# ProPrj___2025-03-14.net
KiCad netlist of a schematic drawn in EasyEDA Pro
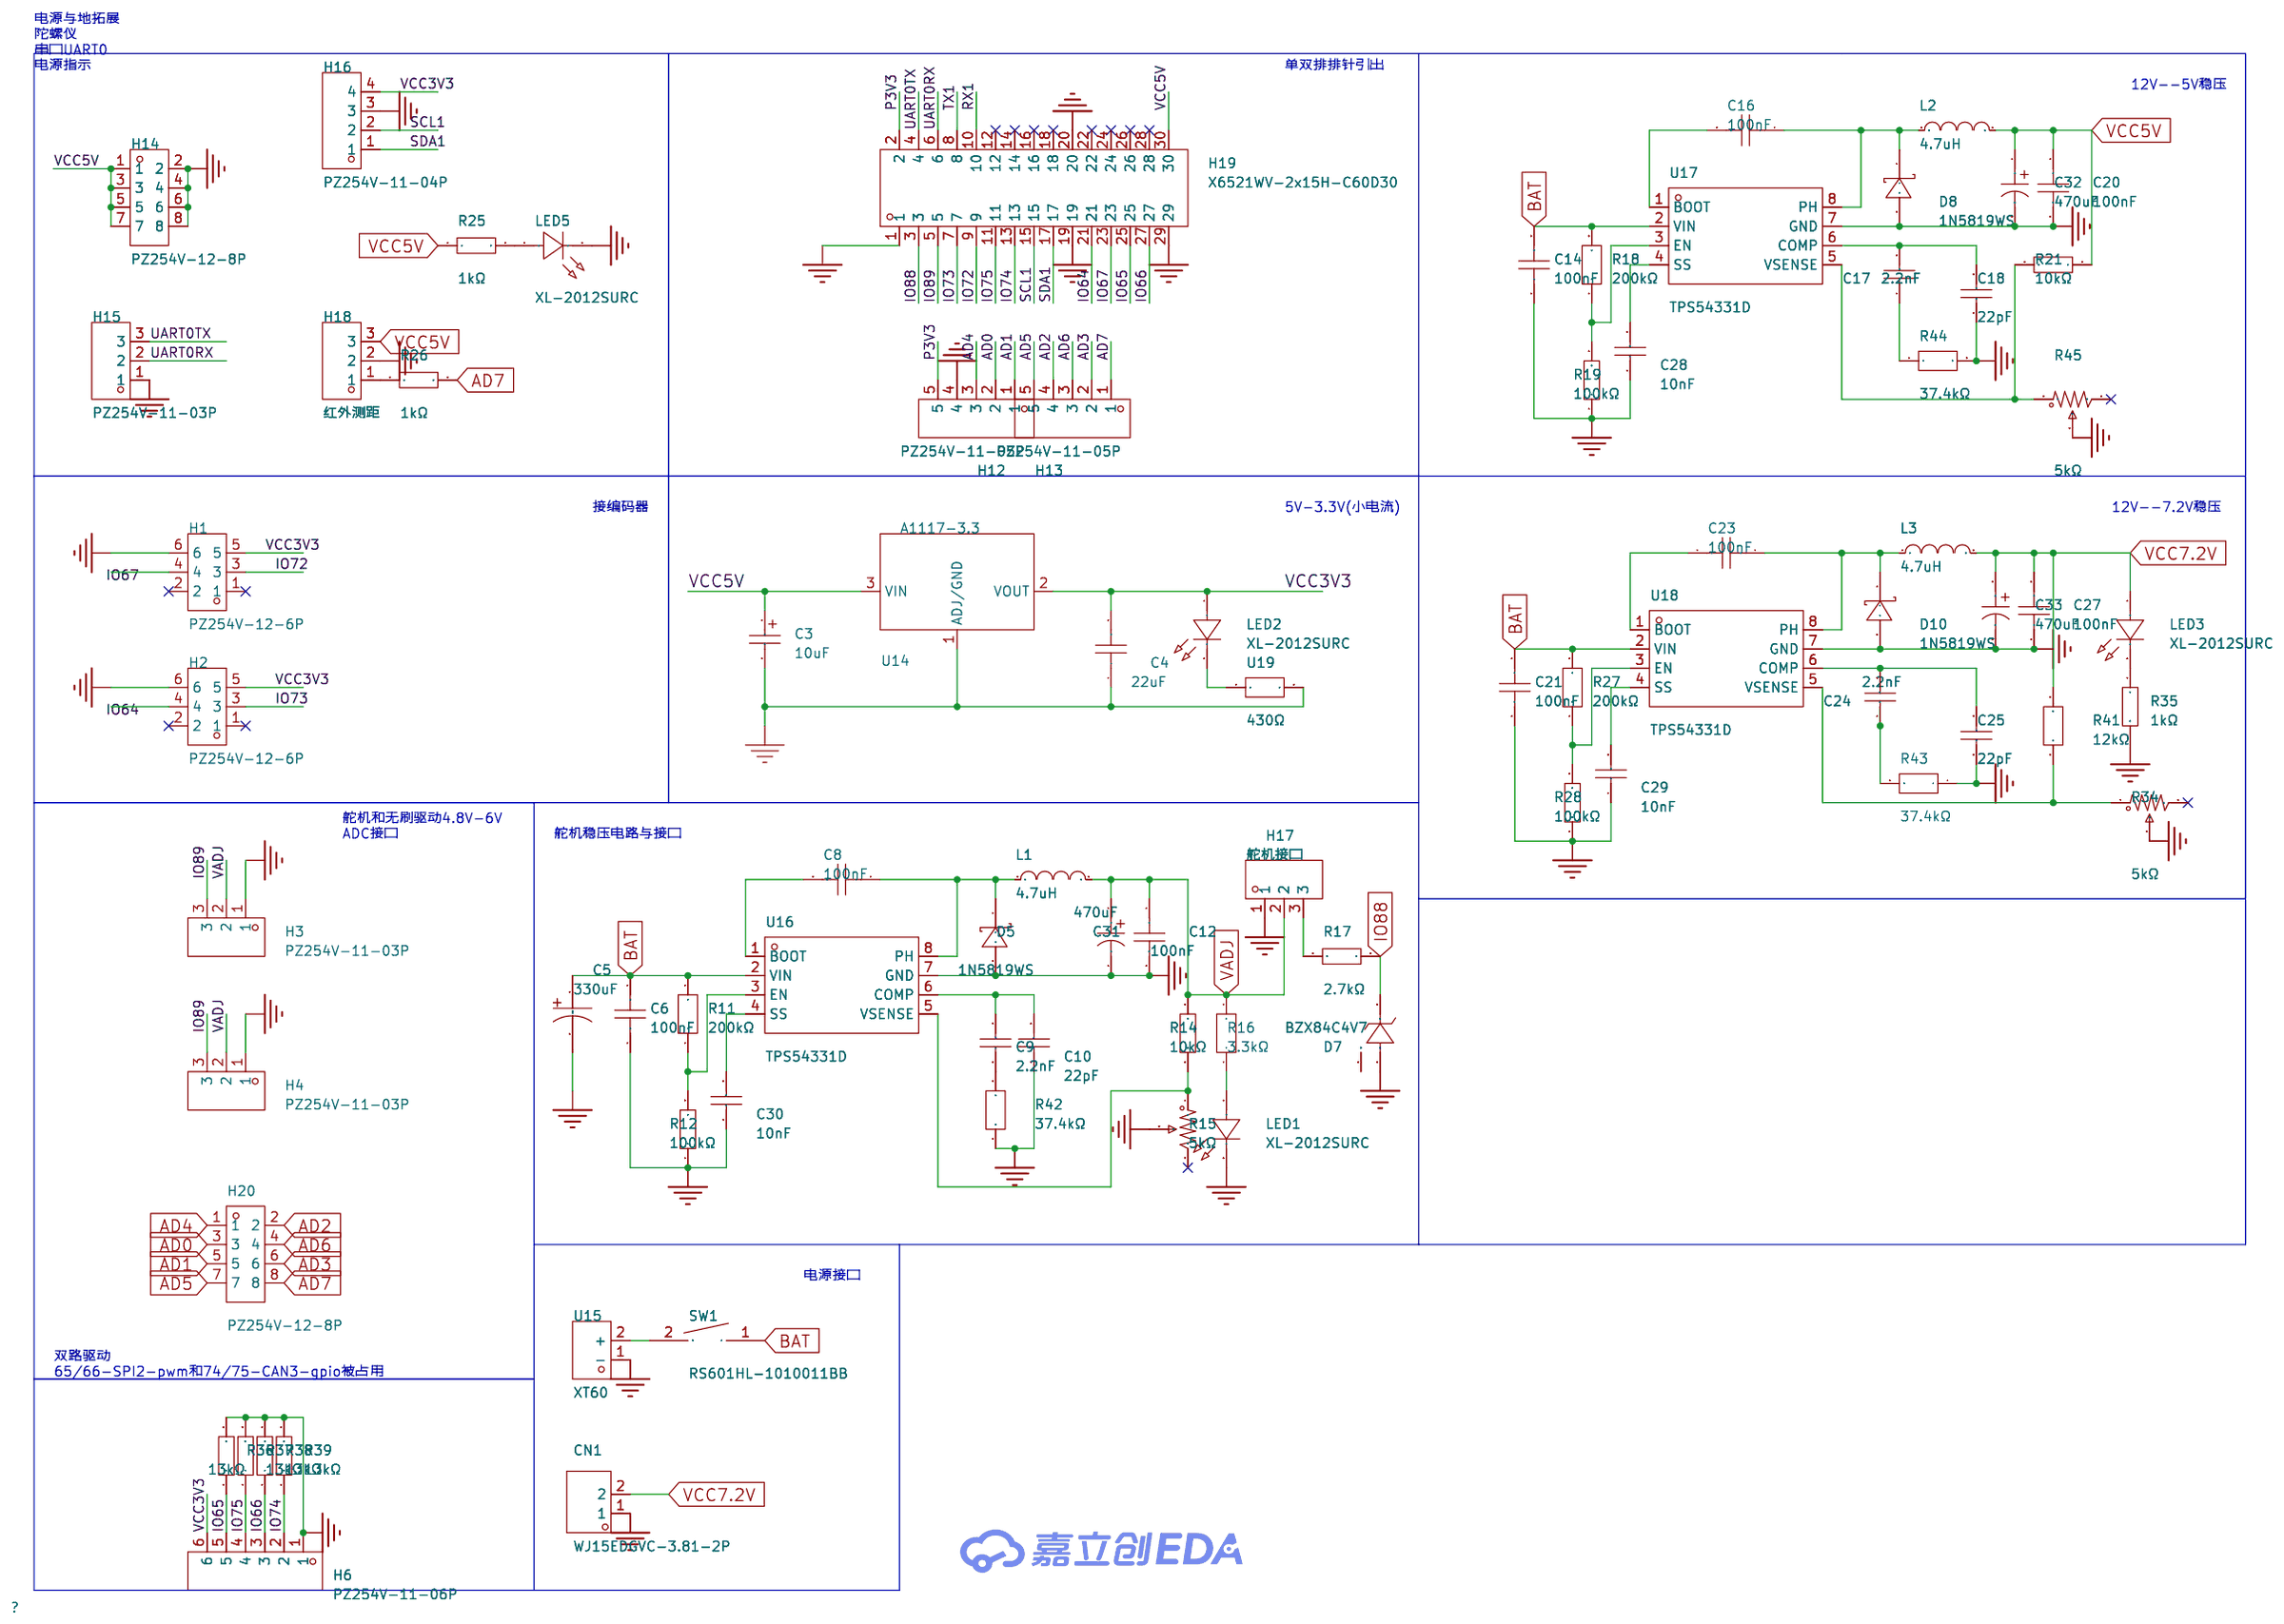
[diagram p0: schematic sheet]

(export (version "E")
  (design (tool "Eeschema 10.0.6"))
  (components
    (comp (ref "C3")
      (value "10uF")
      (footprint "easyedapro:CAP-SMD_L6.0-W3.2")
      (description "容值:10uF;精度:±10%;额定电压:16V;等效串联电阻:2Ω@100kHz;")
      (fields (field (name "Manufacturer Part") "TAJC106K016RNJ") (field (name "Manufacturer") "Kyocera AVX"))
      (libsource (lib "easyedapro") (part "TAJC106K016RNJ"))
    )
    (comp (ref "C4")
      (value "22uF")
      (footprint "easyedapro:C0805")
      (description "容值:22uF;精度:±20%;额定电压:35V;材质(温度系数):X5R;")
      (fields
        (field (name "Manufacturer Part") "CGA0805X5R226M350MT")
        (field (name "Manufacturer") "HRE(芯声)")
      )
      (libsource (lib "easyedapro") (part "CGA0805X5R226M350MT"))
    )
    (comp (ref "C5")
      (value "330uF")
      (footprint "easyedapro:CAP-SMD_BD8.0-L8.3-W8.3-LS9.3-FD-1")
      (description "容值:330uF;精度:±20%;额定电压:25V;纹波电流:228mA@120Hz;等效串联电阻(ESR):-;")
      (fields (field (name "Manufacturer Part") "RVT1E331M0810") (field (name "Manufacturer") "ROQANG(容强)"))
      (libsource (lib "easyedapro") (part "RVT1E331M0810_C335985"))
    )
    (comp (ref "C6")
      (value "100nF")
      (footprint "easyedapro:C0805")
      (description "容值:100nF;精度:±10%;额定电压:50V;材质(温度系数):X7R;")
      (fields
        (field (name "Manufacturer Part") "CC0805KRX7R9BB104")
        (field (name "Manufacturer") "YAGEO(国巨)")
      )
      (libsource (lib "easyedapro") (part "CC0805KRX7R9BB104"))
    )
    (comp (ref "C8")
      (value "100nF")
      (footprint "easyedapro:C0805")
      (description "容值:100nF;精度:±10%;额定电压:50V;材质(温度系数):X7R;")
      (fields
        (field (name "Manufacturer Part") "CC0805KRX7R9BB104")
        (field (name "Manufacturer") "YAGEO(国巨)")
      )
      (libsource (lib "easyedapro") (part "CC0805KRX7R9BB104"))
    )
    (comp (ref "C9")
      (value "2.2nF")
      (footprint "easyedapro:C0805")
      (description "容值:2.2nF;精度:±5%;额定电压:50V;材质(温度系数):C0G;")
      (fields
        (field (name "Manufacturer Part") "CL21C222JBFNNNE")
        (field (name "Manufacturer") "SAMSUNG(三星)")
      )
      (libsource (lib "easyedapro") (part "CL21C222JBFNNNE"))
    )
    (comp (ref "C10")
      (value "22pF")
      (footprint "easyedapro:C0603")
      (description "容值:22pF;精度:±5%;额定电压:50V;材质(温度系数):NP0;")
      (fields
        (field (name "Manufacturer Part") "CC0603JRNPO9BN220")
        (field (name "Manufacturer") "YAGEO(国巨)")
      )
      (libsource (lib "easyedapro") (part "CC0603JRNPO9BN220"))
    )
    (comp (ref "C12")
      (value "100nF")
      (footprint "easyedapro:C0805")
      (description "容值:100nF;精度:±10%;额定电压:50V;材质(温度系数):X7R;")
      (fields
        (field (name "Manufacturer Part") "CC0805KRX7R9BB104")
        (field (name "Manufacturer") "YAGEO(国巨)")
      )
      (libsource (lib "easyedapro") (part "CC0805KRX7R9BB104"))
    )
    (comp (ref "C14")
      (value "100nF")
      (footprint "easyedapro:C0805")
      (description "容值:100nF;精度:±10%;额定电压:50V;材质(温度系数):X7R;")
      (fields
        (field (name "Manufacturer Part") "CC0805KRX7R9BB104")
        (field (name "Manufacturer") "YAGEO(国巨)")
      )
      (libsource (lib "easyedapro") (part "CC0805KRX7R9BB104"))
    )
    (comp (ref "C16")
      (value "100nF")
      (footprint "easyedapro:C0805")
      (description "容值:100nF;精度:±10%;额定电压:50V;材质(温度系数):X7R;")
      (fields
        (field (name "Manufacturer Part") "CC0805KRX7R9BB104")
        (field (name "Manufacturer") "YAGEO(国巨)")
      )
      (libsource (lib "easyedapro") (part "CC0805KRX7R9BB104"))
    )
    (comp (ref "C17")
      (value "2.2nF")
      (footprint "easyedapro:C0805")
      (description "容值:2.2nF;精度:±5%;额定电压:50V;材质(温度系数):C0G;")
      (fields
        (field (name "Manufacturer Part") "CL21C222JBFNNNE")
        (field (name "Manufacturer") "SAMSUNG(三星)")
      )
      (libsource (lib "easyedapro") (part "CL21C222JBFNNNE"))
    )
    (comp (ref "C18")
      (value "22pF")
      (footprint "easyedapro:C0603")
      (description "容值:22pF;精度:±5%;额定电压:50V;材质(温度系数):NP0;")
      (fields
        (field (name "Manufacturer Part") "CC0603JRNPO9BN220")
        (field (name "Manufacturer") "YAGEO(国巨)")
      )
      (libsource (lib "easyedapro") (part "CC0603JRNPO9BN220"))
    )
    (comp (ref "C20")
      (value "100nF")
      (footprint "easyedapro:C0805")
      (description "容值:100nF;精度:±10%;额定电压:50V;材质(温度系数):X7R;")
      (fields
        (field (name "Manufacturer Part") "CC0805KRX7R9BB104")
        (field (name "Manufacturer") "YAGEO(国巨)")
      )
      (libsource (lib "easyedapro") (part "CC0805KRX7R9BB104"))
    )
    (comp (ref "C21")
      (value "100nF")
      (footprint "easyedapro:C0805")
      (description "容值:100nF;精度:±10%;额定电压:50V;材质(温度系数):X7R;")
      (fields
        (field (name "Manufacturer Part") "CC0805KRX7R9BB104")
        (field (name "Manufacturer") "YAGEO(国巨)")
      )
      (libsource (lib "easyedapro") (part "CC0805KRX7R9BB104"))
    )
    (comp (ref "C23")
      (value "100nF")
      (footprint "easyedapro:C0805")
      (description "容值:100nF;精度:±10%;额定电压:50V;材质(温度系数):X7R;")
      (fields
        (field (name "Manufacturer Part") "CC0805KRX7R9BB104")
        (field (name "Manufacturer") "YAGEO(国巨)")
      )
      (libsource (lib "easyedapro") (part "CC0805KRX7R9BB104"))
    )
    (comp (ref "C24")
      (value "2.2nF")
      (footprint "easyedapro:C0805")
      (description "容值:2.2nF;精度:±5%;额定电压:50V;材质(温度系数):C0G;")
      (fields
        (field (name "Manufacturer Part") "CL21C222JBFNNNE")
        (field (name "Manufacturer") "SAMSUNG(三星)")
      )
      (libsource (lib "easyedapro") (part "CL21C222JBFNNNE"))
    )
    (comp (ref "C25")
      (value "22pF")
      (footprint "easyedapro:C0603")
      (description "容值:22pF;精度:±5%;额定电压:50V;材质(温度系数):NP0;")
      (fields
        (field (name "Manufacturer Part") "CC0603JRNPO9BN220")
        (field (name "Manufacturer") "YAGEO(国巨)")
      )
      (libsource (lib "easyedapro") (part "CC0603JRNPO9BN220"))
    )
    (comp (ref "C27")
      (value "100nF")
      (footprint "easyedapro:C0805")
      (description "容值:100nF;精度:±10%;额定电压:50V;材质(温度系数):X7R;")
      (fields
        (field (name "Manufacturer Part") "CC0805KRX7R9BB104")
        (field (name "Manufacturer") "YAGEO(国巨)")
      )
      (libsource (lib "easyedapro") (part "CC0805KRX7R9BB104"))
    )
    (comp (ref "C28")
      (value "10nF")
      (footprint "easyedapro:C0805")
      (description "容值:10nF;精度:±10%;额定电压:50V;材质(温度系数):X7R;")
      (fields
        (field (name "Manufacturer Part") "CL21B103KBANNNC")
        (field (name "Manufacturer") "SAMSUNG(三星)")
      )
      (libsource (lib "easyedapro") (part "CL21B103KBANNNC"))
    )
    (comp (ref "C29")
      (value "10nF")
      (footprint "easyedapro:C0805")
      (description "容值:10nF;精度:±10%;额定电压:50V;材质(温度系数):X7R;")
      (fields
        (field (name "Manufacturer Part") "CL21B103KBANNNC")
        (field (name "Manufacturer") "SAMSUNG(三星)")
      )
      (libsource (lib "easyedapro") (part "CL21B103KBANNNC"))
    )
    (comp (ref "C30")
      (value "10nF")
      (footprint "easyedapro:C0805")
      (description "容值:10nF;精度:±10%;额定电压:50V;材质(温度系数):X7R;")
      (fields
        (field (name "Manufacturer Part") "CL21B103KBANNNC")
        (field (name "Manufacturer") "SAMSUNG(三星)")
      )
      (libsource (lib "easyedapro") (part "CL21B103KBANNNC"))
    )
    (comp (ref "C31")
      (value "470uF")
      (footprint "easyedapro:CAP-SMD_BD8.0-L8.3-W8.3-LS8.9-FD")
      (description "容值:470uF;精度:±20%;额定电压:16V;纹波电流:240mA@120Hz;")
      (fields (field (name "Manufacturer Part") "CK1C471M-CRF10") (field (name "Manufacturer") "ROQANG(容强)"))
      (libsource (lib "easyedapro") (part "CK1C471M-CRF10_C5162359"))
    )
    (comp (ref "C32")
      (value "470uF")
      (footprint "easyedapro:CAP-SMD_BD8.0-L8.3-W8.3-LS8.9-FD")
      (description "容值:470uF;精度:±20%;额定电压:16V;纹波电流:240mA@120Hz;")
      (fields (field (name "Manufacturer Part") "CK1C471M-CRF10") (field (name "Manufacturer") "ROQANG(容强)"))
      (libsource (lib "easyedapro") (part "CK1C471M-CRF10_C5162359"))
    )
    (comp (ref "C33")
      (value "470uF")
      (footprint "easyedapro:CAP-SMD_BD8.0-L8.3-W8.3-LS8.9-FD")
      (description "容值:470uF;精度:±20%;额定电压:16V;纹波电流:240mA@120Hz;")
      (fields (field (name "Manufacturer Part") "CK1C471M-CRF10") (field (name "Manufacturer") "ROQANG(容强)"))
      (libsource (lib "easyedapro") (part "CK1C471M-CRF10_C5162359"))
    )
    (comp (ref "CN1")
      (value "WJ15EDGVC-3.81-2P")
      (footprint "easyedapro:CONN-TH_WJ15EDGVC-3.81-2P")
      (fields (field (name "Manufacturer") "KANGNEX(康奈克斯电气)"))
      (libsource (lib "easyedapro") (part "WJ15EDGVC-3.81-2P"))
    )
    (comp (ref "D5")
      (value "1N5819WS")
      (footprint "easyedapro:SOD-323_L1.8-W1.3-LS2.5-RD")
      (description "正向压降(Vf):600mV@1A;直流反向耐压(Vr):40V;整流电流:1A;")
      (fields (field (name "Manufacturer") "Hottech(合科泰)"))
      (libsource (lib "easyedapro") (part "1N5819WS"))
    )
    (comp (ref "D7")
      (value "BZX84C4V7")
      (footprint "easyedapro:SOT-23-3_L2.9-W1.3-P1.90-LS2.4-BR")
      (description "二极管配置:独立式;稳压值(标称值):4.7V;稳压值(范围):4.4V~5V;耗散功率(Pd):350mW;")
      (fields (field (name "Manufacturer") "LGE(鲁光)"))
      (libsource (lib "easyedapro") (part "BZX84C4V7_C841158"))
    )
    (comp (ref "D8")
      (value "1N5819WS")
      (footprint "easyedapro:SOD-323_L1.8-W1.3-LS2.5-RD")
      (description "正向压降(Vf):600mV@1A;直流反向耐压(Vr):40V;整流电流:1A;")
      (fields (field (name "Manufacturer") "Hottech(合科泰)"))
      (libsource (lib "easyedapro") (part "1N5819WS"))
    )
    (comp (ref "D10")
      (value "1N5819WS")
      (footprint "easyedapro:SOD-323_L1.8-W1.3-LS2.5-RD")
      (description "正向压降(Vf):600mV@1A;直流反向耐压(Vr):40V;整流电流:1A;")
      (fields (field (name "Manufacturer") "Hottech(合科泰)"))
      (libsource (lib "easyedapro") (part "1N5819WS"))
    )
    (comp (ref "H1")
      (value "PZ254V-12-6P")
      (footprint "easyedapro:HDR-TH_6P-P2.54-V-M-R2-C3-S2.54")
      (fields (field (name "Manufacturer") "XFCN(兴飞)"))
      (libsource (lib "easyedapro") (part "PZ254V-12-6P"))
    )
    (comp (ref "H2")
      (value "PZ254V-12-6P")
      (footprint "easyedapro:HDR-TH_6P-P2.54-V-M-R2-C3-S2.54")
      (fields (field (name "Manufacturer") "XFCN(兴飞)"))
      (libsource (lib "easyedapro") (part "PZ254V-12-6P"))
    )
    (comp (ref "H3")
      (value "PZ254V-11-03P")
      (footprint "easyedapro:HDR-TH_3P-P2.54-V-M")
      (fields (field (name "Manufacturer") "XFCN(兴飞)"))
      (libsource (lib "easyedapro") (part "PZ254V-11-03P_C2937625"))
    )
    (comp (ref "H4")
      (value "PZ254V-11-03P")
      (footprint "easyedapro:HDR-TH_3P-P2.54-V-M")
      (fields (field (name "Manufacturer") "XFCN(兴飞)"))
      (libsource (lib "easyedapro") (part "PZ254V-11-03P_C2937625"))
    )
    (comp (ref "H6")
      (value "PZ254V-11-06P")
      (footprint "easyedapro:HDR-TH_6P-P2.54-V-M")
      (fields (field (name "Manufacturer") "XFCN(兴飞)"))
      (libsource (lib "easyedapro") (part "PZ254V-11-06P"))
    )
    (comp (ref "H12")
      (value "PZ254V-11-05P")
      (footprint "easyedapro:HDR-TH_5P-P2.54-V-M")
      (fields (field (name "Manufacturer") "XFCN(兴飞)"))
      (libsource (lib "easyedapro") (part "PZ254V-11-05P"))
    )
    (comp (ref "H13")
      (value "PZ254V-11-05P")
      (footprint "easyedapro:HDR-TH_5P-P2.54-V-M")
      (fields (field (name "Manufacturer") "XFCN(兴飞)"))
      (libsource (lib "easyedapro") (part "PZ254V-11-05P"))
    )
    (comp (ref "H14")
      (value "PZ254V-12-8P")
      (footprint "easyedapro:HDR-TH_8P-P2.54-V-M-R2-C4-S2.54")
      (fields (field (name "Manufacturer") "XFCN(兴飞)"))
      (libsource (lib "easyedapro") (part "PZ254V-12-8P"))
    )
    (comp (ref "H15")
      (value "PZ254V-11-03P")
      (footprint "easyedapro:HDR-TH_3P-P2.54-V-M")
      (fields (field (name "Manufacturer") "XFCN(兴飞)"))
      (libsource (lib "easyedapro") (part "PZ254V-11-03P_C2937625"))
    )
    (comp (ref "H16")
      (value "PZ254V-11-04P")
      (footprint "easyedapro:HDR-TH_4P-P2.54-V-M")
      (fields (field (name "Manufacturer") "XFCN(兴飞)"))
      (libsource (lib "easyedapro") (part "PZ254V-11-04P_C2691448"))
    )
    (comp (ref "H17")
      (value "舵机接口")
      (footprint "easyedapro:HDR-TH_3P-P2.54-V-M")
      (fields (field (name "Manufacturer") "XFCN(兴飞)"))
      (libsource (lib "easyedapro") (part "PZ254V-11-03P_C2937625"))
    )
    (comp (ref "H18")
      (value "红外测距")
      (footprint "easyedapro:HDR-TH_3P-P2.54-V-M")
      (fields (field (name "Manufacturer") "XFCN(兴飞)"))
      (libsource (lib "easyedapro") (part "PZ254V-11-03P_C2937625"))
    )
    (comp (ref "H19")
      (value "X6521WV-2x15H-C60D30")
      (footprint "easyedapro:HDR-TH_30P-P2.54-V-M-R2-C15-S2.54-BL")
      (fields (field (name "Manufacturer") "XKB Connection(中国星坤)"))
      (libsource (lib "easyedapro") (part "X6521WV-2×15H-C30D60"))
    )
    (comp (ref "H20")
      (value "PZ254V-12-8P")
      (footprint "easyedapro:HDR-TH_8P-P2.54-V-M-R2-C4-S2.54")
      (fields (field (name "Manufacturer") "XFCN(兴飞)"))
      (libsource (lib "easyedapro") (part "PZ254V-12-8P"))
    )
    (comp (ref "L1")
      (value "4.7uH")
      (footprint "easyedapro:IND-SMD_L7.3-W6.6_MHCI06030")
      (description "电感值:4.7uH;精度:±20%;额定电流:5.5A;")
      (fields
        (field (name "Manufacturer Part") "SLO0630H4R7MTT")
        (field (name "Manufacturer") "Sunltech(韩国顺磁)")
      )
      (libsource (lib "easyedapro") (part "SLO0630H4R7MTT"))
    )
    (comp (ref "L2")
      (value "4.7uH")
      (footprint "easyedapro:IND-SMD_L7.3-W6.6_MHCI06030")
      (description "电感值:4.7uH;精度:±20%;额定电流:5.5A;")
      (fields
        (field (name "Manufacturer Part") "SLO0630H4R7MTT")
        (field (name "Manufacturer") "Sunltech(韩国顺磁)")
      )
      (libsource (lib "easyedapro") (part "SLO0630H4R7MTT"))
    )
    (comp (ref "L3")
      (value "4.7uH")
      (footprint "easyedapro:IND-SMD_L7.3-W6.6_MHCI06030")
      (description "电感值:4.7uH;精度:±20%;额定电流:5.5A;")
      (fields
        (field (name "Manufacturer Part") "SLO0630H4R7MTT")
        (field (name "Manufacturer") "Sunltech(韩国顺磁)")
      )
      (libsource (lib "easyedapro") (part "SLO0630H4R7MTT"))
    )
    (comp (ref "LED1")
      (value "XL-2012SURC")
      (footprint "easyedapro:LED0805-R-RD")
      (description "发光颜色:红色;功率:55mW;正向电流:25mA;主波长:617nm~621nm;透镜颜色:无色透明透镜;色温:-;发光角度:120°;载带方式:正贴;工作温度:-30°C~+85°C;")
      (fields (field (name "Manufacturer") "XINGLIGHT(成兴光)"))
      (libsource (lib "easyedapro") (part "XL-2012SURC"))
    )
    (comp (ref "LED2")
      (value "XL-2012SURC")
      (footprint "easyedapro:LED0805-R-RD")
      (description "发光颜色:红色;功率:55mW;正向电流:25mA;主波长:617nm~621nm;透镜颜色:无色透明透镜;色温:-;发光角度:120°;载带方式:正贴;工作温度:-30°C~+85°C;")
      (fields (field (name "Manufacturer") "XINGLIGHT(成兴光)"))
      (libsource (lib "easyedapro") (part "XL-2012SURC"))
    )
    (comp (ref "LED3")
      (value "XL-2012SURC")
      (footprint "easyedapro:LED0805-R-RD")
      (description "发光颜色:红色;功率:55mW;正向电流:25mA;主波长:617nm~621nm;透镜颜色:无色透明透镜;色温:-;发光角度:120°;载带方式:正贴;工作温度:-30°C~+85°C;")
      (fields (field (name "Manufacturer") "XINGLIGHT(成兴光)"))
      (libsource (lib "easyedapro") (part "XL-2012SURC"))
    )
    (comp (ref "LED5")
      (value "XL-2012SURC")
      (footprint "easyedapro:LED0805-R-RD")
      (description "发光颜色:红色;功率:55mW;正向电流:25mA;主波长:617nm~621nm;透镜颜色:无色透明透镜;色温:-;发光角度:120°;载带方式:正贴;工作温度:-30°C~+85°C;")
      (fields (field (name "Manufacturer") "XINGLIGHT(成兴光)"))
      (libsource (lib "easyedapro") (part "XL-2012SURC"))
    )
    (comp (ref "R11")
      (value "200kΩ")
      (footprint "easyedapro:R0603")
      (description "电阻类型:厚膜电阻;阻值:200kΩ;精度:±1%;功率:100mW;工作电压:75V;温度系数:±100ppm/°C;")
      (fields (field (name "Manufacturer Part") "FRC0603F2003TS") (field (name "Manufacturer") "FOJAN(富捷)"))
      (libsource (lib "easyedapro") (part "FRC0603F2003TS"))
    )
    (comp (ref "R12")
      (value "100kΩ")
      (footprint "easyedapro:R0805")
      (description "电阻类型:厚膜电阻;阻值:100kΩ;精度:±1%;功率:125mW;最大工作电压:150V;温度系数:±100ppm/°C;")
      (fields
        (field (name "Manufacturer Part") "0805W8F1003T5E")
        (field (name "Manufacturer") "UNI-ROYAL(厚声)")
      )
      (libsource (lib "easyedapro") (part "0805W8F1003T5E_C149504"))
    )
    (comp (ref "R14")
      (value "10kΩ")
      (footprint "easyedapro:R0805")
      (description "电阻类型:厚膜电阻;阻值:10kΩ;精度:±1%;功率:125mW;最大工作电压:150V;温度系数:±100ppm/°C;")
      (fields
        (field (name "Manufacturer Part") "0805W8F1002T5E")
        (field (name "Manufacturer") "UNI-ROYAL(厚声)")
      )
      (libsource (lib "easyedapro") (part "0805W8F1002T5E"))
    )
    (comp (ref "R15")
      (value "5kΩ")
      (footprint "easyedapro:RES-ADJ-TH_3P-L6.8-W4.6-P2.50-TL-BS-3266X")
      (description "阻值:5kΩ;精度:±10%;功率:250mW;温度系数:±100ppm/°C;")
      (fields (field (name "Manufacturer Part") "3266X-1-502LF") (field (name "Manufacturer") "BOURNS"))
      (libsource (lib "easyedapro") (part "3266X-1-502LF"))
    )
    (comp (ref "R16")
      (value "3.3kΩ")
      (footprint "easyedapro:R0805")
      (description "电阻类型:厚膜电阻;阻值:3.3kΩ;精度:±1%;功率:125mW;最大工作电压:150V;温度系数:±100ppm/°C;")
      (fields (field (name "Manufacturer Part") "FRC0805F3301TS") (field (name "Manufacturer") "FOJAN(富捷)"))
      (libsource (lib "easyedapro") (part "FRC0805F3301TS"))
    )
    (comp (ref "R17")
      (value "2.7kΩ")
      (footprint "easyedapro:R0603")
      (description "电阻类型:厚膜电阻;阻值:2.7kΩ;精度:±1%;功率:100mW;最大工作电压:75V;温度系数:±100ppm/°C;")
      (fields
        (field (name "Manufacturer Part") "0603WAF2701T5E")
        (field (name "Manufacturer") "UNI-ROYAL(厚声)")
      )
      (libsource (lib "easyedapro") (part "0603WAF2701T5E"))
    )
    (comp (ref "R18")
      (value "200kΩ")
      (footprint "easyedapro:R0603")
      (description "电阻类型:厚膜电阻;阻值:200kΩ;精度:±1%;功率:100mW;工作电压:75V;温度系数:±100ppm/°C;")
      (fields (field (name "Manufacturer Part") "FRC0603F2003TS") (field (name "Manufacturer") "FOJAN(富捷)"))
      (libsource (lib "easyedapro") (part "FRC0603F2003TS"))
    )
    (comp (ref "R19")
      (value "100kΩ")
      (footprint "easyedapro:R0805")
      (description "电阻类型:厚膜电阻;阻值:100kΩ;精度:±1%;功率:125mW;最大工作电压:150V;温度系数:±100ppm/°C;")
      (fields
        (field (name "Manufacturer Part") "0805W8F1003T5E")
        (field (name "Manufacturer") "UNI-ROYAL(厚声)")
      )
      (libsource (lib "easyedapro") (part "0805W8F1003T5E_C149504"))
    )
    (comp (ref "R21")
      (value "10kΩ")
      (footprint "easyedapro:R0805")
      (description "电阻类型:厚膜电阻;阻值:10kΩ;精度:±1%;功率:125mW;最大工作电压:150V;温度系数:±100ppm/°C;")
      (fields
        (field (name "Manufacturer Part") "0805W8F1002T5E")
        (field (name "Manufacturer") "UNI-ROYAL(厚声)")
      )
      (libsource (lib "easyedapro") (part "0805W8F1002T5E"))
    )
    (comp (ref "R25")
      (value "1kΩ")
      (footprint "easyedapro:R0603")
      (description "电阻类型:厚膜电阻;阻值:1kΩ;精度:±1%;功率:100mW;最大工作电压:75V;温度系数:±100ppm/°C;")
      (fields
        (field (name "Manufacturer Part") "0603WAF1001T5E")
        (field (name "Manufacturer") "UNI-ROYAL(厚声)")
      )
      (libsource (lib "easyedapro") (part "0603WAF1001T5E"))
    )
    (comp (ref "R26")
      (value "1kΩ")
      (footprint "easyedapro:R0603")
      (description "电阻类型:厚膜电阻;阻值:1kΩ;精度:±1%;功率:100mW;最大工作电压:75V;温度系数:±100ppm/°C;")
      (fields
        (field (name "Manufacturer Part") "0603WAF1001T5E")
        (field (name "Manufacturer") "UNI-ROYAL(厚声)")
      )
      (libsource (lib "easyedapro") (part "0603WAF1001T5E"))
    )
    (comp (ref "R27")
      (value "200kΩ")
      (footprint "easyedapro:R0603")
      (description "电阻类型:厚膜电阻;阻值:200kΩ;精度:±1%;功率:100mW;工作电压:75V;温度系数:±100ppm/°C;")
      (fields (field (name "Manufacturer Part") "FRC0603F2003TS") (field (name "Manufacturer") "FOJAN(富捷)"))
      (libsource (lib "easyedapro") (part "FRC0603F2003TS"))
    )
    (comp (ref "R28")
      (value "100kΩ")
      (footprint "easyedapro:R0805")
      (description "电阻类型:厚膜电阻;阻值:100kΩ;精度:±1%;功率:125mW;最大工作电压:150V;温度系数:±100ppm/°C;")
      (fields
        (field (name "Manufacturer Part") "0805W8F1003T5E")
        (field (name "Manufacturer") "UNI-ROYAL(厚声)")
      )
      (libsource (lib "easyedapro") (part "0805W8F1003T5E_C149504"))
    )
    (comp (ref "R34")
      (value "5kΩ")
      (footprint "easyedapro:RES-ADJ-TH_3P-L6.8-W4.6-P2.50-TL-BS-3266X")
      (description "阻值:5kΩ;精度:±10%;功率:250mW;温度系数:±100ppm/°C;")
      (fields (field (name "Manufacturer Part") "3266X-1-502LF") (field (name "Manufacturer") "BOURNS"))
      (libsource (lib "easyedapro") (part "3266X-1-502LF"))
    )
    (comp (ref "R35")
      (value "1kΩ")
      (footprint "easyedapro:R0603")
      (description "电阻类型:厚膜电阻;阻值:510Ω;精度:±1%;功率:100mW;最大工作电压:75V;温度系数:±100ppm/°C;")
      (fields
        (field (name "Manufacturer Part") "0603WAF5100T5E")
        (field (name "Manufacturer") "UNI-ROYAL(厚声)")
      )
      (libsource (lib "easyedapro") (part "0603WAF5100T5E"))
    )
    (comp (ref "R36")
      (value "13kΩ")
      (footprint "easyedapro:R0805")
      (description "电阻类型:厚膜电阻;阻值:13kΩ;精度:±1%;功率:125mW;最大工作电压:150V;温度系数:±100ppm/°C;")
      (fields
        (field (name "Manufacturer Part") "0805W8F1302T5E")
        (field (name "Manufacturer") "UNI-ROYAL(厚声)")
      )
      (libsource (lib "easyedapro") (part "0805W8F1302T5E"))
    )
    (comp (ref "R37")
      (value "13kΩ")
      (footprint "easyedapro:R0805")
      (description "电阻类型:厚膜电阻;阻值:13kΩ;精度:±1%;功率:125mW;最大工作电压:150V;温度系数:±100ppm/°C;")
      (fields
        (field (name "Manufacturer Part") "0805W8F1302T5E")
        (field (name "Manufacturer") "UNI-ROYAL(厚声)")
      )
      (libsource (lib "easyedapro") (part "0805W8F1302T5E"))
    )
    (comp (ref "R38")
      (value "13kΩ")
      (footprint "easyedapro:R0805")
      (description "电阻类型:厚膜电阻;阻值:13kΩ;精度:±1%;功率:125mW;最大工作电压:150V;温度系数:±100ppm/°C;")
      (fields
        (field (name "Manufacturer Part") "0805W8F1302T5E")
        (field (name "Manufacturer") "UNI-ROYAL(厚声)")
      )
      (libsource (lib "easyedapro") (part "0805W8F1302T5E"))
    )
    (comp (ref "R39")
      (value "13kΩ")
      (footprint "easyedapro:R0805")
      (description "电阻类型:厚膜电阻;阻值:13kΩ;精度:±1%;功率:125mW;最大工作电压:150V;温度系数:±100ppm/°C;")
      (fields
        (field (name "Manufacturer Part") "0805W8F1302T5E")
        (field (name "Manufacturer") "UNI-ROYAL(厚声)")
      )
      (libsource (lib "easyedapro") (part "0805W8F1302T5E"))
    )
    (comp (ref "R41")
      (value "12kΩ")
      (footprint "easyedapro:R0805")
      (description "电阻类型:厚膜电阻;阻值:12kΩ;精度:±1%;功率:125mW;最大工作电压:150V;温度系数:±100ppm/°C;")
      (fields (field (name "Manufacturer Part") "FRC0805F1202TS") (field (name "Manufacturer") "FOJAN(富捷)"))
      (libsource (lib "easyedapro") (part "FRC0805F1202TS"))
    )
    (comp (ref "R42")
      (value "37.4kΩ")
      (footprint "easyedapro:R0603")
      (description "电阻类型:薄膜电阻;阻值:37kΩ;精度:±0.25%;功率:100mW;最大工作电压:75V;温度系数:±25ppm/°C;")
      (fields (field (name "Manufacturer Part") "RN73R1JTTD3702C25") (field (name "Manufacturer") "KOA"))
      (libsource (lib "easyedapro") (part "RN73R1JTTD3702C25"))
    )
    (comp (ref "R43")
      (value "37.4kΩ")
      (footprint "easyedapro:R0603")
      (description "电阻类型:薄膜电阻;阻值:37kΩ;精度:±0.25%;功率:100mW;最大工作电压:75V;温度系数:±25ppm/°C;")
      (fields (field (name "Manufacturer Part") "RN73R1JTTD3702C25") (field (name "Manufacturer") "KOA"))
      (libsource (lib "easyedapro") (part "RN73R1JTTD3702C25"))
    )
    (comp (ref "R44")
      (value "37.4kΩ")
      (footprint "easyedapro:R0603")
      (description "电阻类型:薄膜电阻;阻值:37kΩ;精度:±0.25%;功率:100mW;最大工作电压:75V;温度系数:±25ppm/°C;")
      (fields (field (name "Manufacturer Part") "RN73R1JTTD3702C25") (field (name "Manufacturer") "KOA"))
      (libsource (lib "easyedapro") (part "RN73R1JTTD3702C25"))
    )
    (comp (ref "R45")
      (value "5kΩ")
      (footprint "easyedapro:RES-ADJ-TH_3P-L6.8-W4.6-P2.50-TL-BS-3266X")
      (description "阻值:5kΩ;精度:±10%;功率:250mW;温度系数:±100ppm/°C;")
      (fields (field (name "Manufacturer Part") "3266X-1-502LF") (field (name "Manufacturer") "BOURNS"))
      (libsource (lib "easyedapro") (part "3266X-1-502LF"))
    )
    (comp (ref "SW1")
      (value "RS601HL-1010011BB")
      (footprint "easyedapro:SW-TH_RS601HL-1010011BB")
      (description "带灯:无;引脚样式:焊片;额定电流:3A;额定电压(AC):250V;额定电压(DC):-;电路结构:单刀单掷;机械寿命:1万次;")
      (fields (field (name "Manufacturer") "HCTL(华灿天禄)"))
      (libsource (lib "easyedapro") (part "RS601HL-1010011BB"))
    )
    (comp (ref "U14")
      (value "A1117-3.3")
      (footprint "easyedapro:asm1117")
      (fields (field (name "Manufacturer") "IDCHIP(英锐芯)"))
      (libsource (lib "easyedapro") (part "A1117-3.3"))
    )
    (comp (ref "U15")
      (value "XT60")
      (footprint "easyedapro:CONN-TH_XT60")
      (description "类别:-;类型1:-;")
      (fields (field (name "Manufacturer") "AMASS(艾迈斯)"))
      (libsource (lib "easyedapro") (part "XT60"))
    )
    (comp (ref "U16")
      (value "TPS54331D")
      (footprint "easyedapro:SOIC-8_L4.9-W3.9-P1.27-LS6.0-BL")
      (description "功能类型:降压型;输出类型:可调;输入电压:3.5V~28V;输出电压:-;输出电流:3A;")
      (fields (field (name "Manufacturer") "TI(德州仪器)"))
      (libsource (lib "easyedapro") (part "TPS54331D"))
    )
    (comp (ref "U17")
      (value "TPS54331D")
      (footprint "easyedapro:SOIC-8_L4.9-W3.9-P1.27-LS6.0-BL")
      (description "功能类型:降压型;输出类型:可调;输入电压:3.5V~28V;输出电压:-;输出电流:3A;")
      (fields (field (name "Manufacturer") "TI(德州仪器)"))
      (libsource (lib "easyedapro") (part "TPS54331D"))
    )
    (comp (ref "U18")
      (value "TPS54331D")
      (footprint "easyedapro:SOIC-8_L4.9-W3.9-P1.27-LS6.0-BL")
      (description "功能类型:降压型;输出类型:可调;输入电压:3.5V~28V;输出电压:-;输出电流:3A;")
      (fields (field (name "Manufacturer") "TI(德州仪器)"))
      (libsource (lib "easyedapro") (part "TPS54331D"))
    )
    (comp (ref "U19")
      (value "430Ω")
      (footprint "easyedapro:R0805")
      (description "电阻类型:厚膜电阻;阻值:430Ω;精度:±1%;功率:125mW;最大工作电压:150V;温度系数:±100ppm/°C;")
      (fields (field (name "Manufacturer Part") "FRC0805F4300TS") (field (name "Manufacturer") "FOJAN(富捷)"))
      (libsource (lib "easyedapro") (part "FRC0805F4300TS"))
    )
  )
  (nets
    (net (code "1") (name "/IO64") (class "Default")
      (node (ref "H19") (pin "21") (pinfunction "21_21") (pintype "unspecified"))
      (node (ref "H2") (pin "4") (pinfunction "4_4") (pintype "unspecified"))
    )
    (net (code "2") (name "/IO65") (class "Default")
      (node (ref "H19") (pin "25") (pinfunction "25_25") (pintype "unspecified"))
      (node (ref "H6") (pin "5") (pinfunction "5_5") (pintype "unspecified"))
      (node (ref "R36") (pin "1") (pinfunction "1_1") (pintype "input"))
    )
    (net (code "3") (name "/IO66") (class "Default")
      (node (ref "H19") (pin "27") (pinfunction "27_27") (pintype "unspecified"))
      (node (ref "H6") (pin "3") (pinfunction "3_3") (pintype "unspecified"))
      (node (ref "R38") (pin "1") (pinfunction "1_1") (pintype "input"))
    )
    (net (code "4") (name "/IO67") (class "Default")
      (node (ref "H1") (pin "4") (pinfunction "4_4") (pintype "unspecified"))
      (node (ref "H19") (pin "23") (pinfunction "23_23") (pintype "unspecified"))
    )
    (net (code "5") (name "/IO72") (class "Default")
      (node (ref "H1") (pin "3") (pinfunction "3_3") (pintype "unspecified"))
      (node (ref "H19") (pin "9") (pinfunction "9_9") (pintype "unspecified"))
    )
    (net (code "6") (name "/IO73") (class "Default")
      (node (ref "H19") (pin "7") (pinfunction "7_7") (pintype "unspecified"))
      (node (ref "H2") (pin "3") (pinfunction "3_3") (pintype "unspecified"))
    )
    (net (code "7") (name "/IO74") (class "Default")
      (node (ref "H19") (pin "13") (pinfunction "13_13") (pintype "unspecified"))
      (node (ref "H6") (pin "2") (pinfunction "2_2") (pintype "unspecified"))
      (node (ref "R39") (pin "1") (pinfunction "1_1") (pintype "input"))
    )
    (net (code "8") (name "/IO75") (class "Default")
      (node (ref "H19") (pin "11") (pinfunction "11_11") (pintype "unspecified"))
      (node (ref "H6") (pin "4") (pinfunction "4_4") (pintype "unspecified"))
      (node (ref "R37") (pin "1") (pinfunction "1_1") (pintype "input"))
    )
    (net (code "9") (name "/IO89") (class "Default")
      (node (ref "H19") (pin "5") (pinfunction "5_5") (pintype "unspecified"))
      (node (ref "H3") (pin "3") (pinfunction "3_3") (pintype "unspecified"))
      (node (ref "H4") (pin "3") (pinfunction "3_3") (pintype "unspecified"))
    )
    (net (code "10") (name "/P3V3") (class "Default")
      (node (ref "H12") (pin "5") (pinfunction "5_5") (pintype "unspecified"))
      (node (ref "H19") (pin "2") (pinfunction "2_2") (pintype "unspecified"))
    )
    (net (code "11") (name "/RX1") (class "Default")
      (node (ref "H19") (pin "10") (pinfunction "10_10") (pintype "unspecified"))
    )
    (net (code "12") (name "/SCL1") (class "Default")
      (node (ref "H16") (pin "2") (pinfunction "2_2") (pintype "unspecified"))
      (node (ref "H19") (pin "15") (pinfunction "15_15") (pintype "unspecified"))
    )
    (net (code "13") (name "/SDA1") (class "Default")
      (node (ref "H16") (pin "1") (pinfunction "1_1") (pintype "unspecified"))
      (node (ref "H19") (pin "17") (pinfunction "17_17") (pintype "unspecified"))
    )
    (net (code "14") (name "/TX1") (class "Default")
      (node (ref "H19") (pin "8") (pinfunction "8_8") (pintype "unspecified"))
    )
    (net (code "15") (name "/UART0RX") (class "Default")
      (node (ref "H15") (pin "2") (pinfunction "2_2") (pintype "unspecified"))
      (node (ref "H19") (pin "6") (pinfunction "6_6") (pintype "unspecified"))
    )
    (net (code "16") (name "/UART0TX") (class "Default")
      (node (ref "H15") (pin "3") (pinfunction "3_3") (pintype "unspecified"))
      (node (ref "H19") (pin "4") (pinfunction "4_4") (pintype "unspecified"))
    )
    (net (code "17") (name "/VCC3V3") (class "Default")
      (node (ref "C4") (pin "2") (pinfunction "2_2") (pintype "unspecified"))
      (node (ref "H1") (pin "5") (pinfunction "5_5") (pintype "unspecified"))
      (node (ref "H16") (pin "4") (pinfunction "4_4") (pintype "unspecified"))
      (node (ref "H2") (pin "5") (pinfunction "5_5") (pintype "unspecified"))
      (node (ref "H6") (pin "6") (pinfunction "6_6") (pintype "unspecified"))
      (node (ref "LED2") (pin "1") (pinfunction "A_1") (pintype "unspecified"))
      (node (ref "U14") (pin "2") (pinfunction "VOUT_2") (pintype "input"))
    )
    (net (code "18") (name "AD0") (class "Default")
      (node (ref "H12") (pin "2") (pinfunction "2_2") (pintype "unspecified"))
      (node (ref "H20") (pin "3") (pinfunction "3_3") (pintype "unspecified"))
    )
    (net (code "19") (name "AD1") (class "Default")
      (node (ref "H12") (pin "1") (pinfunction "1_1") (pintype "unspecified"))
      (node (ref "H20") (pin "5") (pinfunction "5_5") (pintype "unspecified"))
    )
    (net (code "20") (name "AD2") (class "Default")
      (node (ref "H13") (pin "4") (pinfunction "4_4") (pintype "unspecified"))
      (node (ref "H20") (pin "2") (pinfunction "2_2") (pintype "unspecified"))
    )
    (net (code "21") (name "AD3") (class "Default")
      (node (ref "H13") (pin "2") (pinfunction "2_2") (pintype "unspecified"))
      (node (ref "H20") (pin "6") (pinfunction "6_6") (pintype "unspecified"))
    )
    (net (code "22") (name "AD4") (class "Default")
      (node (ref "H12") (pin "3") (pinfunction "3_3") (pintype "unspecified"))
      (node (ref "H20") (pin "1") (pinfunction "1_1") (pintype "unspecified"))
    )
    (net (code "23") (name "AD5") (class "Default")
      (node (ref "H13") (pin "5") (pinfunction "5_5") (pintype "unspecified"))
      (node (ref "H20") (pin "7") (pinfunction "7_7") (pintype "unspecified"))
    )
    (net (code "24") (name "AD6") (class "Default")
      (node (ref "H13") (pin "3") (pinfunction "3_3") (pintype "unspecified"))
      (node (ref "H20") (pin "4") (pinfunction "4_4") (pintype "unspecified"))
    )
    (net (code "25") (name "AD7") (class "Default")
      (node (ref "H13") (pin "1") (pinfunction "1_1") (pintype "unspecified"))
      (node (ref "H20") (pin "8") (pinfunction "8_8") (pintype "unspecified"))
      (node (ref "R26") (pin "2") (pinfunction "2_2") (pintype "input"))
    )
    (net (code "26") (name "BAT") (class "Default")
      (node (ref "C14") (pin "2") (pinfunction "2_2") (pintype "unspecified"))
      (node (ref "C21") (pin "2") (pinfunction "2_2") (pintype "unspecified"))
      (node (ref "C5") (pin "1") (pinfunction "1_1") (pintype "unspecified"))
      (node (ref "C6") (pin "2") (pinfunction "2_2") (pintype "unspecified"))
      (node (ref "R11") (pin "2") (pinfunction "2_2") (pintype "unspecified"))
      (node (ref "R18") (pin "2") (pinfunction "2_2") (pintype "unspecified"))
      (node (ref "R27") (pin "2") (pinfunction "2_2") (pintype "unspecified"))
      (node (ref "SW1") (pin "1") (pinfunction "1_1") (pintype "input"))
      (node (ref "U16") (pin "2") (pinfunction "VIN_2") (pintype "unspecified"))
      (node (ref "U17") (pin "2") (pinfunction "VIN_2") (pintype "unspecified"))
      (node (ref "U18") (pin "2") (pinfunction "VIN_2") (pintype "unspecified"))
    )
    (net (code "27") (name "GND") (class "Default")
      (node (ref "C10") (pin "1") (pinfunction "1_1") (pintype "input"))
      (node (ref "C12") (pin "2") (pinfunction "2_2") (pintype "unspecified"))
      (node (ref "C14") (pin "1") (pinfunction "1_1") (pintype "unspecified"))
      (node (ref "C18") (pin "1") (pinfunction "1_1") (pintype "input"))
      (node (ref "C20") (pin "2") (pinfunction "2_2") (pintype "unspecified"))
      (node (ref "C21") (pin "1") (pinfunction "1_1") (pintype "unspecified"))
      (node (ref "C25") (pin "1") (pinfunction "1_1") (pintype "input"))
      (node (ref "C27") (pin "2") (pinfunction "2_2") (pintype "unspecified"))
      (node (ref "C28") (pin "1") (pinfunction "1_1") (pintype "input"))
      (node (ref "C29") (pin "1") (pinfunction "1_1") (pintype "input"))
      (node (ref "C3") (pin "2") (pinfunction "2_2") (pintype "input"))
      (node (ref "C30") (pin "1") (pinfunction "1_1") (pintype "input"))
      (node (ref "C31") (pin "2") (pinfunction "2_2") (pintype "input"))
      (node (ref "C32") (pin "2") (pinfunction "2_2") (pintype "input"))
      (node (ref "C33") (pin "2") (pinfunction "2_2") (pintype "input"))
      (node (ref "C4") (pin "1") (pinfunction "1_1") (pintype "unspecified"))
      (node (ref "C5") (pin "2") (pinfunction "2_2") (pintype "unspecified"))
      (node (ref "C6") (pin "1") (pinfunction "1_1") (pintype "unspecified"))
      (node (ref "CN1") (pin "1") (pinfunction "1_1") (pintype "unspecified"))
      (node (ref "D10") (pin "2") (pinfunction "A_2") (pintype "unspecified"))
      (node (ref "D5") (pin "2") (pinfunction "A_2") (pintype "unspecified"))
      (node (ref "D7") (pin "1") (pinfunction "A_1") (pintype "unspecified"))
      (node (ref "D8") (pin "2") (pinfunction "A_2") (pintype "unspecified"))
      (node (ref "H1") (pin "6") (pinfunction "6_6") (pintype "unspecified"))
      (node (ref "H12") (pin "4") (pinfunction "4_4") (pintype "unspecified"))
      (node (ref "H14") (pin "2") (pinfunction "2_2") (pintype "unspecified"))
      (node (ref "H14") (pin "4") (pinfunction "4_4") (pintype "unspecified"))
      (node (ref "H14") (pin "6") (pinfunction "6_6") (pintype "unspecified"))
      (node (ref "H14") (pin "8") (pinfunction "8_8") (pintype "unspecified"))
      (node (ref "H15") (pin "1") (pinfunction "1_1") (pintype "unspecified"))
      (node (ref "H16") (pin "3") (pinfunction "3_3") (pintype "unspecified"))
      (node (ref "H17") (pin "1") (pinfunction "1_1") (pintype "unspecified"))
      (node (ref "H18") (pin "2") (pinfunction "2_2") (pintype "unspecified"))
      (node (ref "H19") (pin "1") (pinfunction "1_1") (pintype "unspecified"))
      (node (ref "H19") (pin "19") (pinfunction "19_19") (pintype "unspecified"))
      (node (ref "H19") (pin "20") (pinfunction "20_20") (pintype "unspecified"))
      (node (ref "H19") (pin "29") (pinfunction "29_29") (pintype "unspecified"))
      (node (ref "H2") (pin "6") (pinfunction "6_6") (pintype "unspecified"))
      (node (ref "H3") (pin "1") (pinfunction "1_1") (pintype "unspecified"))
      (node (ref "H4") (pin "1") (pinfunction "1_1") (pintype "unspecified"))
      (node (ref "H6") (pin "1") (pinfunction "1_1") (pintype "unspecified"))
      (node (ref "LED1") (pin "2") (pinfunction "K_2") (pintype "unspecified"))
      (node (ref "LED5") (pin "2") (pinfunction "K_2") (pintype "unspecified"))
      (node (ref "R12") (pin "1") (pinfunction "1_1") (pintype "unspecified"))
      (node (ref "R15") (pin "2") (pinfunction "2_2") (pintype "unspecified"))
      (node (ref "R19") (pin "1") (pinfunction "1_1") (pintype "unspecified"))
      (node (ref "R28") (pin "1") (pinfunction "1_1") (pintype "unspecified"))
      (node (ref "R34") (pin "2") (pinfunction "2_2") (pintype "unspecified"))
      (node (ref "R35") (pin "2") (pinfunction "2_2") (pintype "input"))
      (node (ref "R36") (pin "2") (pinfunction "2_2") (pintype "input"))
      (node (ref "R37") (pin "2") (pinfunction "2_2") (pintype "input"))
      (node (ref "R38") (pin "2") (pinfunction "2_2") (pintype "input"))
      (node (ref "R39") (pin "2") (pinfunction "2_2") (pintype "input"))
      (node (ref "R42") (pin "1") (pinfunction "1_1") (pintype "unspecified"))
      (node (ref "R43") (pin "1") (pinfunction "1_1") (pintype "unspecified"))
      (node (ref "R44") (pin "2") (pinfunction "2_2") (pintype "unspecified"))
      (node (ref "R45") (pin "2") (pinfunction "2_2") (pintype "unspecified"))
      (node (ref "U14") (pin "1") (pinfunction "ADJ/GND_1") (pintype "input"))
      (node (ref "U15") (pin "1") (pinfunction "-_1") (pintype "unspecified"))
      (node (ref "U16") (pin "7") (pinfunction "GND_7") (pintype "unspecified"))
      (node (ref "U17") (pin "7") (pinfunction "GND_7") (pintype "unspecified"))
      (node (ref "U18") (pin "7") (pinfunction "GND_7") (pintype "unspecified"))
      (node (ref "U19") (pin "2") (pinfunction "2_2") (pintype "unspecified"))
    )
    (net (code "28") (name "IO88") (class "Default")
      (node (ref "D7") (pin "3") (pinfunction "C_3") (pintype "unspecified"))
      (node (ref "H19") (pin "3") (pinfunction "3_3") (pintype "unspecified"))
      (node (ref "R17") (pin "1") (pinfunction "1_1") (pintype "input"))
    )
    (net (code "29") (name "Net-(C9-Pad1)") (class "Default")
      (node (ref "C9") (pin "1") (pinfunction "1_1") (pintype "input"))
      (node (ref "R42") (pin "2") (pinfunction "2_2") (pintype "unspecified"))
    )
    (net (code "30") (name "Net-(C17-Pad1)") (class "Default")
      (node (ref "C17") (pin "1") (pinfunction "1_1") (pintype "input"))
      (node (ref "R44") (pin "1") (pinfunction "1_1") (pintype "unspecified"))
    )
    (net (code "31") (name "Net-(C24-Pad1)") (class "Default")
      (node (ref "C24") (pin "1") (pinfunction "1_1") (pintype "input"))
      (node (ref "R43") (pin "2") (pinfunction "2_2") (pintype "unspecified"))
    )
    (net (code "32") (name "Net-(D5-K)") (class "Default")
      (node (ref "C8") (pin "1") (pinfunction "1_1") (pintype "unspecified"))
      (node (ref "D5") (pin "1") (pinfunction "K_1") (pintype "unspecified"))
      (node (ref "L1") (pin "1") (pinfunction "1_1") (pintype "unspecified"))
      (node (ref "U16") (pin "8") (pinfunction "PH_8") (pintype "unspecified"))
    )
    (net (code "33") (name "Net-(D8-K)") (class "Default")
      (node (ref "C16") (pin "1") (pinfunction "1_1") (pintype "unspecified"))
      (node (ref "D8") (pin "1") (pinfunction "K_1") (pintype "unspecified"))
      (node (ref "L2") (pin "1") (pinfunction "1_1") (pintype "unspecified"))
      (node (ref "U17") (pin "8") (pinfunction "PH_8") (pintype "unspecified"))
    )
    (net (code "34") (name "Net-(D10-K)") (class "Default")
      (node (ref "C23") (pin "1") (pinfunction "1_1") (pintype "unspecified"))
      (node (ref "D10") (pin "1") (pinfunction "K_1") (pintype "unspecified"))
      (node (ref "L3") (pin "1") (pinfunction "1_1") (pintype "unspecified"))
      (node (ref "U18") (pin "8") (pinfunction "PH_8") (pintype "unspecified"))
    )
    (net (code "35") (name "Net-(H17-Pad3)") (class "Default")
      (node (ref "H17") (pin "3") (pinfunction "3_3") (pintype "unspecified"))
      (node (ref "R17") (pin "2") (pinfunction "2_2") (pintype "input"))
    )
    (net (code "36") (name "Net-(H18-Pad1)") (class "Default")
      (node (ref "H18") (pin "1") (pinfunction "1_1") (pintype "unspecified"))
      (node (ref "R26") (pin "1") (pinfunction "1_1") (pintype "input"))
    )
    (net (code "37") (name "Net-(LED1-A)") (class "Default")
      (node (ref "LED1") (pin "1") (pinfunction "A_1") (pintype "unspecified"))
      (node (ref "R16") (pin "1") (pinfunction "1_1") (pintype "unspecified"))
    )
    (net (code "38") (name "Net-(LED2-K)") (class "Default")
      (node (ref "LED2") (pin "2") (pinfunction "K_2") (pintype "unspecified"))
      (node (ref "U19") (pin "1") (pinfunction "1_1") (pintype "unspecified"))
    )
    (net (code "39") (name "Net-(LED3-K)") (class "Default")
      (node (ref "LED3") (pin "2") (pinfunction "K_2") (pintype "unspecified"))
      (node (ref "R35") (pin "1") (pinfunction "1_1") (pintype "input"))
    )
    (net (code "40") (name "Net-(LED5-A)") (class "Default")
      (node (ref "LED5") (pin "1") (pinfunction "A_1") (pintype "unspecified"))
      (node (ref "R25") (pin "2") (pinfunction "2_2") (pintype "input"))
    )
    (net (code "41") (name "Net-(U15-+)") (class "Default")
      (node (ref "SW1") (pin "2") (pinfunction "2_2") (pintype "input"))
      (node (ref "U15") (pin "2") (pinfunction "+_2") (pintype "unspecified"))
    )
    (net (code "42") (name "Net-(U16-BOOT)") (class "Default")
      (node (ref "C8") (pin "2") (pinfunction "2_2") (pintype "unspecified"))
      (node (ref "U16") (pin "1") (pinfunction "BOOT_1") (pintype "unspecified"))
    )
    (net (code "43") (name "Net-(U16-COMP)") (class "Default")
      (node (ref "C10") (pin "2") (pinfunction "2_2") (pintype "input"))
      (node (ref "C9") (pin "2") (pinfunction "2_2") (pintype "input"))
      (node (ref "U16") (pin "6") (pinfunction "COMP_6") (pintype "unspecified"))
    )
    (net (code "44") (name "Net-(U16-EN)") (class "Default")
      (node (ref "R11") (pin "1") (pinfunction "1_1") (pintype "unspecified"))
      (node (ref "R12") (pin "2") (pinfunction "2_2") (pintype "unspecified"))
      (node (ref "U16") (pin "3") (pinfunction "EN_3") (pintype "unspecified"))
    )
    (net (code "45") (name "Net-(U16-SS)") (class "Default")
      (node (ref "C30") (pin "2") (pinfunction "2_2") (pintype "input"))
      (node (ref "U16") (pin "4") (pinfunction "SS_4") (pintype "unspecified"))
    )
    (net (code "46") (name "Net-(U16-VSENSE)") (class "Default")
      (node (ref "R14") (pin "1") (pinfunction "1_1") (pintype "input"))
      (node (ref "R15") (pin "1") (pinfunction "1_1") (pintype "unspecified"))
      (node (ref "U16") (pin "5") (pinfunction "VSENSE_5") (pintype "unspecified"))
    )
    (net (code "47") (name "Net-(U17-BOOT)") (class "Default")
      (node (ref "C16") (pin "2") (pinfunction "2_2") (pintype "unspecified"))
      (node (ref "U17") (pin "1") (pinfunction "BOOT_1") (pintype "unspecified"))
    )
    (net (code "48") (name "Net-(U17-COMP)") (class "Default")
      (node (ref "C17") (pin "2") (pinfunction "2_2") (pintype "input"))
      (node (ref "C18") (pin "2") (pinfunction "2_2") (pintype "input"))
      (node (ref "U17") (pin "6") (pinfunction "COMP_6") (pintype "unspecified"))
    )
    (net (code "49") (name "Net-(U17-EN)") (class "Default")
      (node (ref "R18") (pin "1") (pinfunction "1_1") (pintype "unspecified"))
      (node (ref "R19") (pin "2") (pinfunction "2_2") (pintype "unspecified"))
      (node (ref "U17") (pin "3") (pinfunction "EN_3") (pintype "unspecified"))
    )
    (net (code "50") (name "Net-(U17-SS)") (class "Default")
      (node (ref "C28") (pin "2") (pinfunction "2_2") (pintype "input"))
      (node (ref "U17") (pin "4") (pinfunction "SS_4") (pintype "unspecified"))
    )
    (net (code "51") (name "Net-(U17-VSENSE)") (class "Default")
      (node (ref "R21") (pin "2") (pinfunction "2_2") (pintype "input"))
      (node (ref "R45") (pin "1") (pinfunction "1_1") (pintype "unspecified"))
      (node (ref "U17") (pin "5") (pinfunction "VSENSE_5") (pintype "unspecified"))
    )
    (net (code "52") (name "Net-(U18-BOOT)") (class "Default")
      (node (ref "C23") (pin "2") (pinfunction "2_2") (pintype "unspecified"))
      (node (ref "U18") (pin "1") (pinfunction "BOOT_1") (pintype "unspecified"))
    )
    (net (code "53") (name "Net-(U18-COMP)") (class "Default")
      (node (ref "C24") (pin "2") (pinfunction "2_2") (pintype "input"))
      (node (ref "C25") (pin "2") (pinfunction "2_2") (pintype "input"))
      (node (ref "U18") (pin "6") (pinfunction "COMP_6") (pintype "unspecified"))
    )
    (net (code "54") (name "Net-(U18-EN)") (class "Default")
      (node (ref "R27") (pin "1") (pinfunction "1_1") (pintype "unspecified"))
      (node (ref "R28") (pin "2") (pinfunction "2_2") (pintype "unspecified"))
      (node (ref "U18") (pin "3") (pinfunction "EN_3") (pintype "unspecified"))
    )
    (net (code "55") (name "Net-(U18-SS)") (class "Default")
      (node (ref "C29") (pin "2") (pinfunction "2_2") (pintype "input"))
      (node (ref "U18") (pin "4") (pinfunction "SS_4") (pintype "unspecified"))
    )
    (net (code "56") (name "Net-(U18-VSENSE)") (class "Default")
      (node (ref "R34") (pin "1") (pinfunction "1_1") (pintype "unspecified"))
      (node (ref "R41") (pin "1") (pinfunction "1_1") (pintype "unspecified"))
      (node (ref "U18") (pin "5") (pinfunction "VSENSE_5") (pintype "unspecified"))
    )
    (net (code "57") (name "VADJ") (class "Default")
      (node (ref "C12") (pin "1") (pinfunction "1_1") (pintype "unspecified"))
      (node (ref "C31") (pin "1") (pinfunction "1_1") (pintype "input"))
      (node (ref "H17") (pin "2") (pinfunction "2_2") (pintype "unspecified"))
      (node (ref "H3") (pin "2") (pinfunction "2_2") (pintype "unspecified"))
      (node (ref "H4") (pin "2") (pinfunction "2_2") (pintype "unspecified"))
      (node (ref "L1") (pin "2") (pinfunction "2_2") (pintype "unspecified"))
      (node (ref "R14") (pin "2") (pinfunction "2_2") (pintype "input"))
      (node (ref "R16") (pin "2") (pinfunction "2_2") (pintype "unspecified"))
    )
    (net (code "58") (name "VCC5V") (class "Default")
      (node (ref "C20") (pin "1") (pinfunction "1_1") (pintype "unspecified"))
      (node (ref "C3") (pin "1") (pinfunction "1_1") (pintype "input"))
      (node (ref "C32") (pin "1") (pinfunction "1_1") (pintype "input"))
      (node (ref "H14") (pin "1") (pinfunction "1_1") (pintype "unspecified"))
      (node (ref "H14") (pin "3") (pinfunction "3_3") (pintype "unspecified"))
      (node (ref "H14") (pin "5") (pinfunction "5_5") (pintype "unspecified"))
      (node (ref "H14") (pin "7") (pinfunction "7_7") (pintype "unspecified"))
      (node (ref "H18") (pin "3") (pinfunction "3_3") (pintype "unspecified"))
      (node (ref "H19") (pin "30") (pinfunction "30_30") (pintype "unspecified"))
      (node (ref "L2") (pin "2") (pinfunction "2_2") (pintype "unspecified"))
      (node (ref "R21") (pin "1") (pinfunction "1_1") (pintype "input"))
      (node (ref "R25") (pin "1") (pinfunction "1_1") (pintype "input"))
      (node (ref "U14") (pin "3") (pinfunction "VIN_3") (pintype "input"))
    )
    (net (code "59") (name "VCC7.2V") (class "Default")
      (node (ref "C27") (pin "1") (pinfunction "1_1") (pintype "unspecified"))
      (node (ref "C33") (pin "1") (pinfunction "1_1") (pintype "input"))
      (node (ref "CN1") (pin "2") (pinfunction "2_2") (pintype "unspecified"))
      (node (ref "L3") (pin "2") (pinfunction "2_2") (pintype "unspecified"))
      (node (ref "LED3") (pin "1") (pinfunction "A_1") (pintype "unspecified"))
      (node (ref "R41") (pin "2") (pinfunction "2_2") (pintype "unspecified"))
    )
    (net (code "60") (name "unconnected-(D7-NC-Pad2)") (class "Default")
      (node (ref "D7") (pin "2") (pinfunction "NC_2") (pintype "unspecified"))
    )
    (net (code "61") (name "unconnected-(H1-Pad1)") (class "Default")
      (node (ref "H1") (pin "1") (pinfunction "1_1") (pintype "unspecified+no_connect"))
    )
    (net (code "62") (name "unconnected-(H1-Pad2)") (class "Default")
      (node (ref "H1") (pin "2") (pinfunction "2_2") (pintype "unspecified+no_connect"))
    )
    (net (code "63") (name "unconnected-(H2-Pad1)") (class "Default")
      (node (ref "H2") (pin "1") (pinfunction "1_1") (pintype "unspecified+no_connect"))
    )
    (net (code "64") (name "unconnected-(H2-Pad2)") (class "Default")
      (node (ref "H2") (pin "2") (pinfunction "2_2") (pintype "unspecified+no_connect"))
    )
    (net (code "65") (name "unconnected-(H19-Pad12)") (class "Default")
      (node (ref "H19") (pin "12") (pinfunction "12_12") (pintype "unspecified+no_connect"))
    )
    (net (code "66") (name "unconnected-(H19-Pad14)") (class "Default")
      (node (ref "H19") (pin "14") (pinfunction "14_14") (pintype "unspecified+no_connect"))
    )
    (net (code "67") (name "unconnected-(H19-Pad16)") (class "Default")
      (node (ref "H19") (pin "16") (pinfunction "16_16") (pintype "unspecified+no_connect"))
    )
    (net (code "68") (name "unconnected-(H19-Pad18)") (class "Default")
      (node (ref "H19") (pin "18") (pinfunction "18_18") (pintype "unspecified+no_connect"))
    )
    (net (code "69") (name "unconnected-(H19-Pad22)") (class "Default")
      (node (ref "H19") (pin "22") (pinfunction "22_22") (pintype "unspecified+no_connect"))
    )
    (net (code "70") (name "unconnected-(H19-Pad24)") (class "Default")
      (node (ref "H19") (pin "24") (pinfunction "24_24") (pintype "unspecified+no_connect"))
    )
    (net (code "71") (name "unconnected-(H19-Pad26)") (class "Default")
      (node (ref "H19") (pin "26") (pinfunction "26_26") (pintype "unspecified+no_connect"))
    )
    (net (code "72") (name "unconnected-(H19-Pad28)") (class "Default")
      (node (ref "H19") (pin "28") (pinfunction "28_28") (pintype "unspecified+no_connect"))
    )
    (net (code "73") (name "unconnected-(R15-Pad3)") (class "Default")
      (node (ref "R15") (pin "3") (pinfunction "3_3") (pintype "unspecified+no_connect"))
    )
    (net (code "74") (name "unconnected-(R34-Pad3)") (class "Default")
      (node (ref "R34") (pin "3") (pinfunction "3_3") (pintype "unspecified+no_connect"))
    )
    (net (code "75") (name "unconnected-(R45-Pad3)") (class "Default")
      (node (ref "R45") (pin "3") (pinfunction "3_3") (pintype "unspecified+no_connect"))
    )
  )
)
